# Hall_Latch.net
KiCad netlist of a schematic drawn in Altium Designer
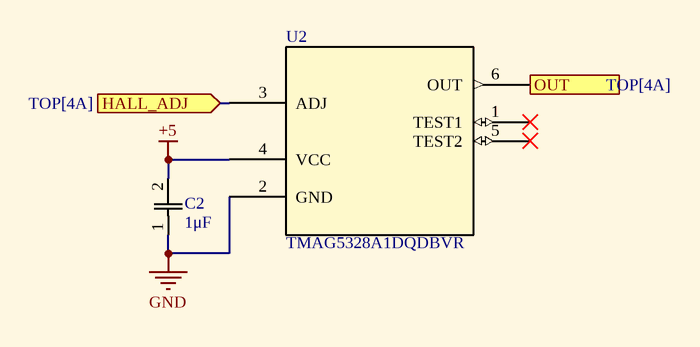
[diagram p0: Hall_Latch.SchDoc]

(export (version "E")
  (design (tool "Eeschema 10.0.6"))
  (components
    (comp (ref "C2")
      (value "1μF")
      (footprint "CAP_CL10_SAM")
      (description "No Description Available")
      (libsource (lib "Component_Schematics") (part "CL10B104KB8NNWC"))
    )
    (comp (ref "U2")
      (value "TMAG5328A1DQDBVR")
      (footprint "SOT23_DBV_TEX")
      (description "No Description Available")
      (fields (field (name "COPYRIGHT") "Copyright (C) 2023 Ultra Librarian. All rights reserved."))
      (libsource (lib "Component_Schematics") (part "TMAG5328A1DQDBVR"))
    )
  )
  (nets
    (net (code "1") (name "+5") (class "Default")
      (node (ref "C2") (pin "2") (pinfunction "2_2") (pintype "passive"))
      (node (ref "U2") (pin "4") (pinfunction "VCC_4") (pintype "power_in"))
    )
    (net (code "2") (name "/HALL_ADJ") (class "Default")
      (node (ref "U2") (pin "3") (pinfunction "ADJ_3") (pintype "passive"))
    )
    (net (code "3") (name "/OUT") (class "Default")
      (node (ref "U2") (pin "6") (pinfunction "OUT_6") (pintype "output"))
    )
    (net (code "4") (name "GND") (class "Default")
      (node (ref "C2") (pin "1") (pinfunction "1_1") (pintype "passive"))
      (node (ref "U2") (pin "2") (pinfunction "GND_2") (pintype "power_in"))
    )
    (net (code "5") (name "unconnected-(U2-TEST1-Pad1)") (class "Default")
      (node (ref "U2") (pin "1") (pinfunction "TEST1_1") (pintype "bidirectional+no_connect"))
    )
    (net (code "6") (name "unconnected-(U2-TEST2-Pad5)") (class "Default")
      (node (ref "U2") (pin "5") (pinfunction "TEST2_5") (pintype "bidirectional+no_connect"))
    )
  )
)
